# DSO_Power.net
KiCad netlist of a schematic drawn in Altium Designer
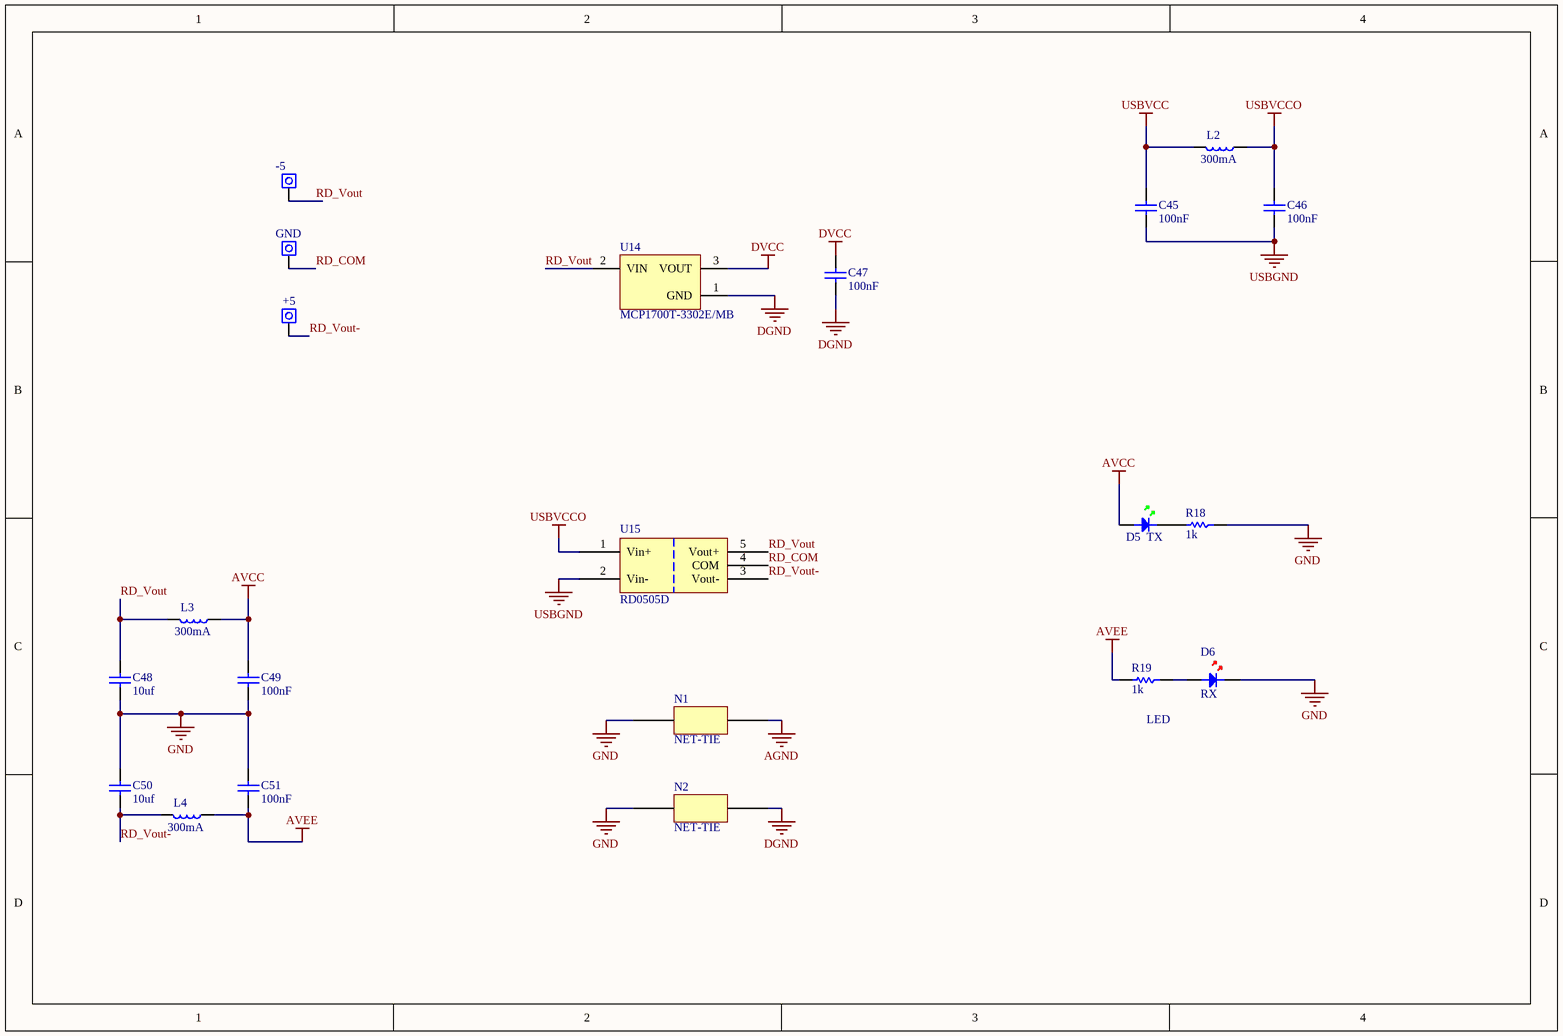
[diagram p0: DSO_Power.SchDoc]

(export (version "E")
  (design (tool "Eeschema 10.0.6"))
  (components
    (comp (ref "C45")
      (value "100nF")
      (footprint "0805C")
      (description "Capacitor")
      (fields (field (name "REVIEWED BY") "RM - 2018/08/05"))
      (libsource (lib "DSO") (part "C"))
    )
    (comp (ref "C46")
      (value "100nF")
      (footprint "0805C")
      (description "Capacitor")
      (fields (field (name "REVIEWED BY") "RM - 2018/08/05"))
      (libsource (lib "DSO") (part "C"))
    )
    (comp (ref "C47")
      (value "100nF")
      (footprint "0805C")
      (description "Capacitor")
      (fields (field (name "REVIEWED BY") "RM - 2018/08/05"))
      (libsource (lib "DSO") (part "C"))
    )
    (comp (ref "C48")
      (value "10uf")
      (footprint "0805C")
      (description "Capacitor")
      (fields (field (name "REVIEWED BY") "RM - 2018/08/05"))
      (libsource (lib "DSO") (part "C"))
    )
    (comp (ref "C49")
      (value "100nF")
      (footprint "0805C")
      (description "Capacitor")
      (fields (field (name "REVIEWED BY") "RM - 2018/08/05"))
      (libsource (lib "DSO") (part "C"))
    )
    (comp (ref "C50")
      (value "10uf")
      (footprint "0805C")
      (description "Capacitor")
      (fields (field (name "REVIEWED BY") "RM - 2018/08/05"))
      (libsource (lib "DSO") (part "C"))
    )
    (comp (ref "C51")
      (value "100nF")
      (footprint "0805C")
      (description "Capacitor")
      (fields (field (name "REVIEWED BY") "RM - 2018/08/05"))
      (libsource (lib "DSO") (part "C"))
    )
    (comp (ref "D5")
      (value "TX")
      (footprint "0805D-GREEN")
      (description "Light Emitting Diode")
      (fields (field (name "REVIEWED BY") "RM - 2018/08/05"))
      (libsource (lib "DSO") (part "LED GREEN"))
    )
    (comp (ref "D6")
      (value "RX")
      (footprint "0805D-RED")
      (description "Light Emitting Diode")
      (fields (field (name "REVIEWED BY") "RM - 2018/08/05"))
      (libsource (lib "DSO") (part "LED RED"))
    )
    (comp (ref "L2")
      (value "300mA")
      (footprint "0805")
      (description "Inductor")
      (fields (field (name "REVIEWED BY") "RM - 2018/08/05"))
      (libsource (lib "DSO") (part "I"))
    )
    (comp (ref "L3")
      (value "300mA")
      (footprint "0805")
      (description "Inductor")
      (fields (field (name "REVIEWED BY") "RM - 2018/08/05"))
      (libsource (lib "DSO") (part "I"))
    )
    (comp (ref "L4")
      (value "300mA")
      (footprint "0805")
      (description "Inductor")
      (fields (field (name "REVIEWED BY") "RM - 2018/08/05"))
      (libsource (lib "DSO") (part "I"))
    )
    (comp (ref "N1") (value "NET-TIE") (footprint "NET-TIE") (libsource (lib "RPOT") (part "NET-TIE")))
    (comp (ref "N2") (value "NET-TIE") (footprint "NET-TIE") (libsource (lib "RPOT") (part "NET-TIE")))
    (comp (ref "R18")
      (value "1k")
      (footprint "0805")
      (description "Resistor")
      (fields (field (name "REVIEWED BY") "RM - 2018/08/05"))
      (libsource (lib "DSO") (part "R"))
    )
    (comp (ref "R19")
      (value "1k")
      (footprint "0805")
      (description "Resistor")
      (fields (field (name "REVIEWED BY") "RM - 2018/08/05"))
      (libsource (lib "DSO") (part "R"))
    )
    (comp (ref "TP4")
      (value "-5")
      (footprint "PIN 1.8mm")
      (description "Pad")
      (libsource (lib "DSO") (part "WIRE"))
    )
    (comp (ref "TP5")
      (value "GND")
      (footprint "PIN 1.8mm")
      (description "Pad")
      (libsource (lib "DSO") (part "WIRE"))
    )
    (comp (ref "TP6")
      (value "+5")
      (footprint "PIN 1.8mm")
      (description "Pad")
      (libsource (lib "DSO") (part "WIRE"))
    )
    (comp (ref "U14")
      (value "MCP1700T-3302E/MB")
      (footprint "SOT89")
      (description "Low Quiescent Current LDO, 3-Pin SOT-89, Extended Temperature, Tape and Reel")
      (fields (field (name "REVIEWED BY") "RM - 2018/08/05"))
      (libsource (lib "DSO") (part "MCP1700T"))
    )
    (comp (ref "U15")
      (value "RD0505D")
      (footprint "SIP_NMG")
      (description "(ADV) DC to DC converter 5V in +-5V out")
      (fields (field (name "REVIEWED BY") "RM - 2018/08/05"))
      (libsource (lib "DSO") (part "RD0505D"))
    )
  )
  (nets
    (net (code "1") (name "/RD_COM") (class "Default")
      (node (ref "TP5") (pin "1") (pintype "passive"))
      (node (ref "U15") (pin "4") (pinfunction "COM_4") (pintype "passive"))
    )
    (net (code "2") (name "/RD_Vout") (class "Default")
      (node (ref "C48") (pin "1") (pinfunction "1_1") (pintype "passive"))
      (node (ref "L3") (pin "2") (pinfunction "2_2") (pintype "passive"))
      (node (ref "TP4") (pin "1") (pintype "passive"))
      (node (ref "U14") (pin "2") (pinfunction "VIN_2") (pintype "power_in"))
      (node (ref "U15") (pin "5") (pinfunction "Vout+_5") (pintype "passive"))
    )
    (net (code "3") (name "/RD_Vout-") (class "Default")
      (node (ref "C50") (pin "2") (pinfunction "2_2") (pintype "passive"))
      (node (ref "L4") (pin "2") (pinfunction "2_2") (pintype "passive"))
      (node (ref "TP6") (pin "1") (pintype "passive"))
      (node (ref "U15") (pin "3") (pinfunction "Vout-_3") (pintype "passive"))
    )
    (net (code "4") (name "AGND") (class "Default")
      (node (ref "N1") (pin "1") (pinfunction "1_1") (pintype "passive"))
    )
    (net (code "5") (name "AVCC") (class "Default")
      (node (ref "C49") (pin "1") (pinfunction "1_1") (pintype "passive"))
      (node (ref "D5") (pin "A") (pinfunction "A_A") (pintype "passive"))
      (node (ref "L3") (pin "1") (pinfunction "1_1") (pintype "passive"))
    )
    (net (code "6") (name "AVEE") (class "Default")
      (node (ref "C51") (pin "2") (pinfunction "2_2") (pintype "passive"))
      (node (ref "L4") (pin "1") (pinfunction "1_1") (pintype "passive"))
      (node (ref "R19") (pin "2") (pintype "passive"))
    )
    (net (code "7") (name "DGND") (class "Default")
      (node (ref "C47") (pin "2") (pinfunction "2_2") (pintype "passive"))
      (node (ref "N2") (pin "1") (pinfunction "1_1") (pintype "passive"))
      (node (ref "U14") (pin "1") (pinfunction "GND_1") (pintype "power_in"))
    )
    (net (code "8") (name "DVCC") (class "Default")
      (node (ref "C47") (pin "1") (pinfunction "1_1") (pintype "passive"))
      (node (ref "U14") (pin "3") (pinfunction "VOUT_3") (pintype "power_in"))
    )
    (net (code "9") (name "GND") (class "Default")
      (node (ref "C48") (pin "2") (pinfunction "2_2") (pintype "passive"))
      (node (ref "C49") (pin "2") (pinfunction "2_2") (pintype "passive"))
      (node (ref "C50") (pin "1") (pinfunction "1_1") (pintype "passive"))
      (node (ref "C51") (pin "1") (pinfunction "1_1") (pintype "passive"))
      (node (ref "D6") (pin "A") (pinfunction "A_A") (pintype "passive"))
      (node (ref "N1") (pin "0") (pinfunction "0_0") (pintype "passive"))
      (node (ref "N2") (pin "0") (pinfunction "0_0") (pintype "passive"))
      (node (ref "R18") (pin "1") (pintype "passive"))
    )
    (net (code "10") (name "Net-(D5-PadK)") (class "Default")
      (node (ref "D5") (pin "K") (pinfunction "K_K") (pintype "passive"))
      (node (ref "R18") (pin "2") (pintype "passive"))
    )
    (net (code "11") (name "Net-(D6-PadK)") (class "Default")
      (node (ref "D6") (pin "K") (pinfunction "K_K") (pintype "passive"))
      (node (ref "R19") (pin "1") (pintype "passive"))
    )
    (net (code "12") (name "USBGND") (class "Default")
      (node (ref "C45") (pin "2") (pinfunction "2_2") (pintype "passive"))
      (node (ref "C46") (pin "2") (pinfunction "2_2") (pintype "passive"))
      (node (ref "U15") (pin "2") (pinfunction "Vin-_2") (pintype "passive"))
    )
    (net (code "13") (name "USBVCC") (class "Default")
      (node (ref "C45") (pin "1") (pinfunction "1_1") (pintype "passive"))
      (node (ref "L2") (pin "2") (pinfunction "2_2") (pintype "passive"))
    )
    (net (code "14") (name "USBVCCO") (class "Default")
      (node (ref "C46") (pin "1") (pinfunction "1_1") (pintype "passive"))
      (node (ref "L2") (pin "1") (pinfunction "1_1") (pintype "passive"))
      (node (ref "U15") (pin "1") (pinfunction "Vin+_1") (pintype "passive"))
    )
  )
)
